# design_project_sch.net
KiCad netlist of a schematic drawn in EAGLE
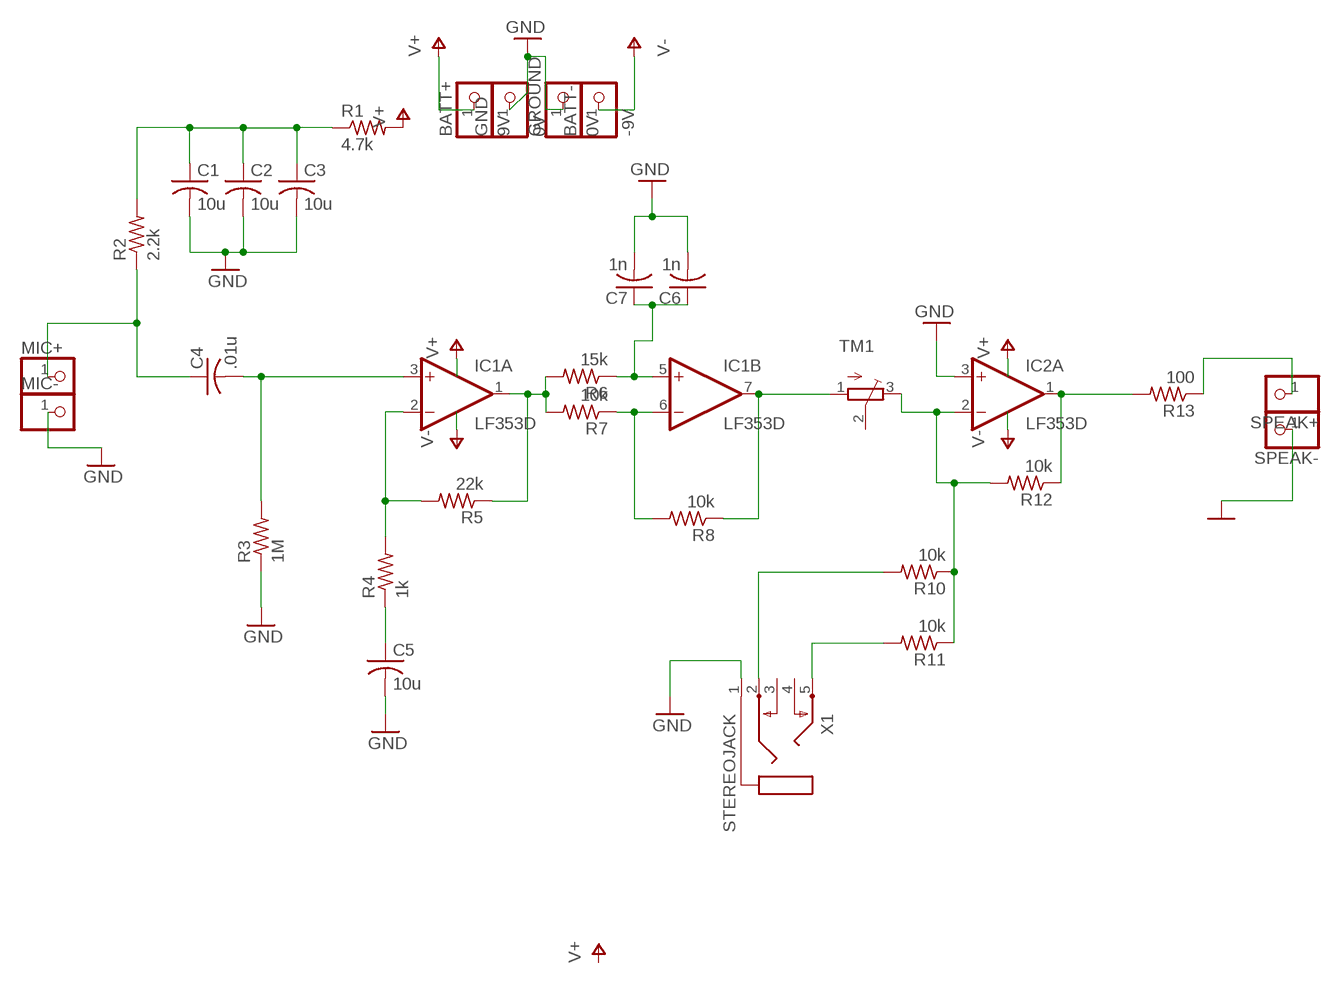
[diagram p0: schematic, sheet 1]

(export (version "E")
  (design (tool "Eeschema 10.0.6"))
  (components
    (comp (ref "BATT+")
      (value "9V")
      (footprint "eagle-import:1X01")
      (libsource (lib "eagle-import") (part "PINHD-1X1"))
    )
    (comp (ref "BATT-")
      (value "-9V")
      (footprint "eagle-import:1X01")
      (libsource (lib "eagle-import") (part "PINHD-1X1"))
    )
    (comp (ref "C1")
      (value "10u")
      (footprint "eagle-import:C0805")
      (libsource (lib "eagle-import") (part "C-USC0805"))
    )
    (comp (ref "C2")
      (value "10u")
      (footprint "eagle-import:C0805")
      (libsource (lib "eagle-import") (part "C-USC0805"))
    )
    (comp (ref "C3")
      (value "10u")
      (footprint "eagle-import:C0805")
      (libsource (lib "eagle-import") (part "C-USC0805"))
    )
    (comp (ref "C4")
      (value ".01u")
      (footprint "eagle-import:C0805")
      (libsource (lib "eagle-import") (part "C-USC0805"))
    )
    (comp (ref "C5")
      (value "10u")
      (footprint "eagle-import:C0805")
      (libsource (lib "eagle-import") (part "C-USC0805"))
    )
    (comp (ref "C6")
      (value "1n")
      (footprint "eagle-import:C0805")
      (libsource (lib "eagle-import") (part "C-USC0805"))
    )
    (comp (ref "C7")
      (value "1n")
      (footprint "eagle-import:C0805")
      (libsource (lib "eagle-import") (part "C-USC0805"))
    )
    (comp (ref "GND")
      (value "0V")
      (footprint "eagle-import:1X01")
      (libsource (lib "eagle-import") (part "PINHD-1X1"))
    )
    (comp (ref "GROUND")
      (value "0V")
      (footprint "eagle-import:1X01")
      (libsource (lib "eagle-import") (part "PINHD-1X1"))
    )
    (comp (ref "IC1")
      (value "LF353D")
      (footprint "eagle-import:SO08")
      (libsource (lib "eagle-import") (part "LF353D"))
    )
    (comp (ref "IC2")
      (value "LF353D")
      (footprint "eagle-import:SO08")
      (libsource (lib "eagle-import") (part "LF353D"))
    )
    (comp (ref "MIC+")
      (value "PINHD-1X1")
      (footprint "eagle-import:1X01")
      (libsource (lib "eagle-import") (part "PINHD-1X1"))
    )
    (comp (ref "MIC-")
      (value "PINHD-1X1")
      (footprint "eagle-import:1X01")
      (libsource (lib "eagle-import") (part "PINHD-1X1"))
    )
    (comp (ref "R1")
      (value "4.7k")
      (footprint "eagle-import:M0805")
      (libsource (lib "eagle-import") (part "R-US_M0805"))
    )
    (comp (ref "R2")
      (value "2.2k")
      (footprint "eagle-import:M0805")
      (libsource (lib "eagle-import") (part "R-US_M0805"))
    )
    (comp (ref "R3")
      (value "1M")
      (footprint "eagle-import:M0805")
      (libsource (lib "eagle-import") (part "R-US_M0805"))
    )
    (comp (ref "R4")
      (value "1k")
      (footprint "eagle-import:M0805")
      (libsource (lib "eagle-import") (part "R-US_M0805"))
    )
    (comp (ref "R5")
      (value "22k")
      (footprint "eagle-import:M0805")
      (libsource (lib "eagle-import") (part "R-US_M0805"))
    )
    (comp (ref "R6")
      (value "15k")
      (footprint "eagle-import:M0805")
      (libsource (lib "eagle-import") (part "R-US_M0805"))
    )
    (comp (ref "R7")
      (value "10k")
      (footprint "eagle-import:M0805")
      (libsource (lib "eagle-import") (part "R-US_M0805"))
    )
    (comp (ref "R8")
      (value "10k")
      (footprint "eagle-import:M0805")
      (libsource (lib "eagle-import") (part "R-US_M0805"))
    )
    (comp (ref "R10")
      (value "10k")
      (footprint "eagle-import:M0805")
      (libsource (lib "eagle-import") (part "R-US_M0805"))
    )
    (comp (ref "R11")
      (value "10k")
      (footprint "eagle-import:M0805")
      (libsource (lib "eagle-import") (part "R-US_M0805"))
    )
    (comp (ref "R12")
      (value "10k")
      (footprint "eagle-import:M0805")
      (libsource (lib "eagle-import") (part "R-US_M0805"))
    )
    (comp (ref "R13")
      (value "100")
      (footprint "eagle-import:M0805")
      (libsource (lib "eagle-import") (part "R-US_M0805"))
    )
    (comp (ref "SPEAK+")
      (value "PINHD-1X1")
      (footprint "eagle-import:1X01")
      (libsource (lib "eagle-import") (part "PINHD-1X1"))
    )
    (comp (ref "SPEAK-")
      (value "PINHD-1X1")
      (footprint "eagle-import:1X01")
      (libsource (lib "eagle-import") (part "PINHD-1X1"))
    )
    (comp (ref "TM1")
      (value "TRIMPOT3386")
      (footprint "eagle-import:TRIM-3386")
      (libsource (lib "eagle-import") (part "TRIMPOT3386"))
    )
    (comp (ref "X1")
      (value "STEREOJACK")
      (footprint "eagle-import:STX3100")
      (libsource (lib "eagle-import") (part "STEREOJACK"))
    )
  )
  (nets
    (net (code "1") (name "GND") (class "Default")
      (node (ref "C1") (pin "2") (pinfunction "2_2") (pintype "passive"))
      (node (ref "C2") (pin "2") (pinfunction "2_2") (pintype "passive"))
      (node (ref "C3") (pin "2") (pinfunction "2_2") (pintype "passive"))
      (node (ref "C5") (pin "2") (pinfunction "2_2") (pintype "passive"))
      (node (ref "C6") (pin "2") (pinfunction "2_2") (pintype "passive"))
      (node (ref "C7") (pin "2") (pinfunction "2_2") (pintype "passive"))
      (node (ref "GND") (pin "1") (pinfunction "1_1") (pintype "passive"))
      (node (ref "GROUND") (pin "1") (pinfunction "1_1") (pintype "passive"))
      (node (ref "IC2") (pin "3") (pinfunction "+IN_3") (pintype "input"))
      (node (ref "MIC-") (pin "1") (pinfunction "1_1") (pintype "passive"))
      (node (ref "R3") (pin "1") (pinfunction "1_1") (pintype "passive"))
      (node (ref "SPEAK-") (pin "1") (pinfunction "1_1") (pintype "passive"))
      (node (ref "X1") (pin "1") (pinfunction "1_1") (pintype "passive"))
    )
    (net (code "2") (name "Net-(C1-Pad1)") (class "Default")
      (node (ref "C1") (pin "1") (pinfunction "1_1") (pintype "passive"))
      (node (ref "C2") (pin "1") (pinfunction "1_1") (pintype "passive"))
      (node (ref "C3") (pin "1") (pinfunction "1_1") (pintype "passive"))
      (node (ref "R1") (pin "1") (pinfunction "1_1") (pintype "passive"))
      (node (ref "R2") (pin "2") (pinfunction "2_2") (pintype "passive"))
    )
    (net (code "3") (name "Net-(C4-Pad1)") (class "Default")
      (node (ref "C4") (pin "1") (pinfunction "1_1") (pintype "passive"))
      (node (ref "MIC+") (pin "1") (pinfunction "1_1") (pintype "passive"))
      (node (ref "R2") (pin "1") (pinfunction "1_1") (pintype "passive"))
    )
    (net (code "4") (name "Net-(C5-Pad1)") (class "Default")
      (node (ref "C5") (pin "1") (pinfunction "1_1") (pintype "passive"))
      (node (ref "R4") (pin "1") (pinfunction "1_1") (pintype "passive"))
    )
    (net (code "5") (name "Net-(IC1A-+IN)") (class "Default")
      (node (ref "C4") (pin "2") (pinfunction "2_2") (pintype "passive"))
      (node (ref "IC1") (pin "3") (pinfunction "+IN_3") (pintype "input"))
      (node (ref "R3") (pin "2") (pinfunction "2_2") (pintype "passive"))
    )
    (net (code "6") (name "Net-(IC1A--IN)") (class "Default")
      (node (ref "IC1") (pin "2") (pinfunction "-IN_2") (pintype "input"))
      (node (ref "R4") (pin "2") (pinfunction "2_2") (pintype "passive"))
      (node (ref "R5") (pin "2") (pinfunction "2_2") (pintype "passive"))
    )
    (net (code "7") (name "Net-(IC1A-OUT)") (class "Default")
      (node (ref "IC1") (pin "1") (pinfunction "OUT_1") (pintype "output"))
      (node (ref "R5") (pin "1") (pinfunction "1_1") (pintype "passive"))
      (node (ref "R6") (pin "2") (pinfunction "2_2") (pintype "passive"))
      (node (ref "R7") (pin "2") (pinfunction "2_2") (pintype "passive"))
    )
    (net (code "8") (name "Net-(IC1B-+IN)") (class "Default")
      (node (ref "C6") (pin "1") (pinfunction "1_1") (pintype "passive"))
      (node (ref "C7") (pin "1") (pinfunction "1_1") (pintype "passive"))
      (node (ref "IC1") (pin "5") (pinfunction "+IN_5") (pintype "input"))
      (node (ref "R6") (pin "1") (pinfunction "1_1") (pintype "passive"))
    )
    (net (code "9") (name "Net-(IC1B--IN)") (class "Default")
      (node (ref "IC1") (pin "6") (pinfunction "-IN_6") (pintype "input"))
      (node (ref "R7") (pin "1") (pinfunction "1_1") (pintype "passive"))
      (node (ref "R8") (pin "2") (pinfunction "2_2") (pintype "passive"))
    )
    (net (code "10") (name "Net-(IC1B-OUT)") (class "Default")
      (node (ref "IC1") (pin "7") (pinfunction "OUT_7") (pintype "output"))
      (node (ref "R8") (pin "1") (pinfunction "1_1") (pintype "passive"))
      (node (ref "TM1") (pin "1") (pinfunction "A_1") (pintype "passive"))
    )
    (net (code "11") (name "Net-(IC2A--IN)") (class "Default")
      (node (ref "IC2") (pin "2") (pinfunction "-IN_2") (pintype "input"))
      (node (ref "R10") (pin "1") (pinfunction "1_1") (pintype "passive"))
      (node (ref "R11") (pin "1") (pinfunction "1_1") (pintype "passive"))
      (node (ref "R12") (pin "2") (pinfunction "2_2") (pintype "passive"))
      (node (ref "TM1") (pin "3") (pinfunction "E_3") (pintype "passive"))
    )
    (net (code "12") (name "Net-(IC2A-OUT)") (class "Default")
      (node (ref "IC2") (pin "1") (pinfunction "OUT_1") (pintype "output"))
      (node (ref "R12") (pin "1") (pinfunction "1_1") (pintype "passive"))
      (node (ref "R13") (pin "2") (pinfunction "2_2") (pintype "passive"))
    )
    (net (code "13") (name "Net-(R10-Pad2)") (class "Default")
      (node (ref "R10") (pin "2") (pinfunction "2_2") (pintype "passive"))
      (node (ref "X1") (pin "2") (pinfunction "2_2") (pintype "passive"))
    )
    (net (code "14") (name "Net-(R11-Pad2)") (class "Default")
      (node (ref "R11") (pin "2") (pinfunction "2_2") (pintype "passive"))
      (node (ref "X1") (pin "5") (pinfunction "5_5") (pintype "passive"))
    )
    (net (code "15") (name "Net-(R13-Pad1)") (class "Default")
      (node (ref "R13") (pin "1") (pinfunction "1_1") (pintype "passive"))
      (node (ref "SPEAK+") (pin "1") (pinfunction "1_1") (pintype "passive"))
    )
    (net (code "16") (name "V+") (class "Default")
      (node (ref "BATT+") (pin "1") (pinfunction "1_1") (pintype "passive"))
      (node (ref "R1") (pin "2") (pinfunction "2_2") (pintype "passive"))
    )
    (net (code "17") (name "V-") (class "Default")
      (node (ref "BATT-") (pin "1") (pinfunction "1_1") (pintype "passive"))
    )
    (net (code "18") (name "unconnected-(TM1-S-Pad2)") (class "Default")
      (node (ref "TM1") (pin "2") (pinfunction "S_2") (pintype "passive"))
    )
    (net (code "19") (name "unconnected-(X1-Pad3)") (class "Default")
      (node (ref "X1") (pin "3") (pinfunction "3_3") (pintype "passive"))
    )
    (net (code "20") (name "unconnected-(X1-Pad4)") (class "Default")
      (node (ref "X1") (pin "4") (pinfunction "4_4") (pintype "passive"))
    )
  )
)
